# 06_POWER_2.net
KiCad netlist of a schematic drawn in Altium Designer
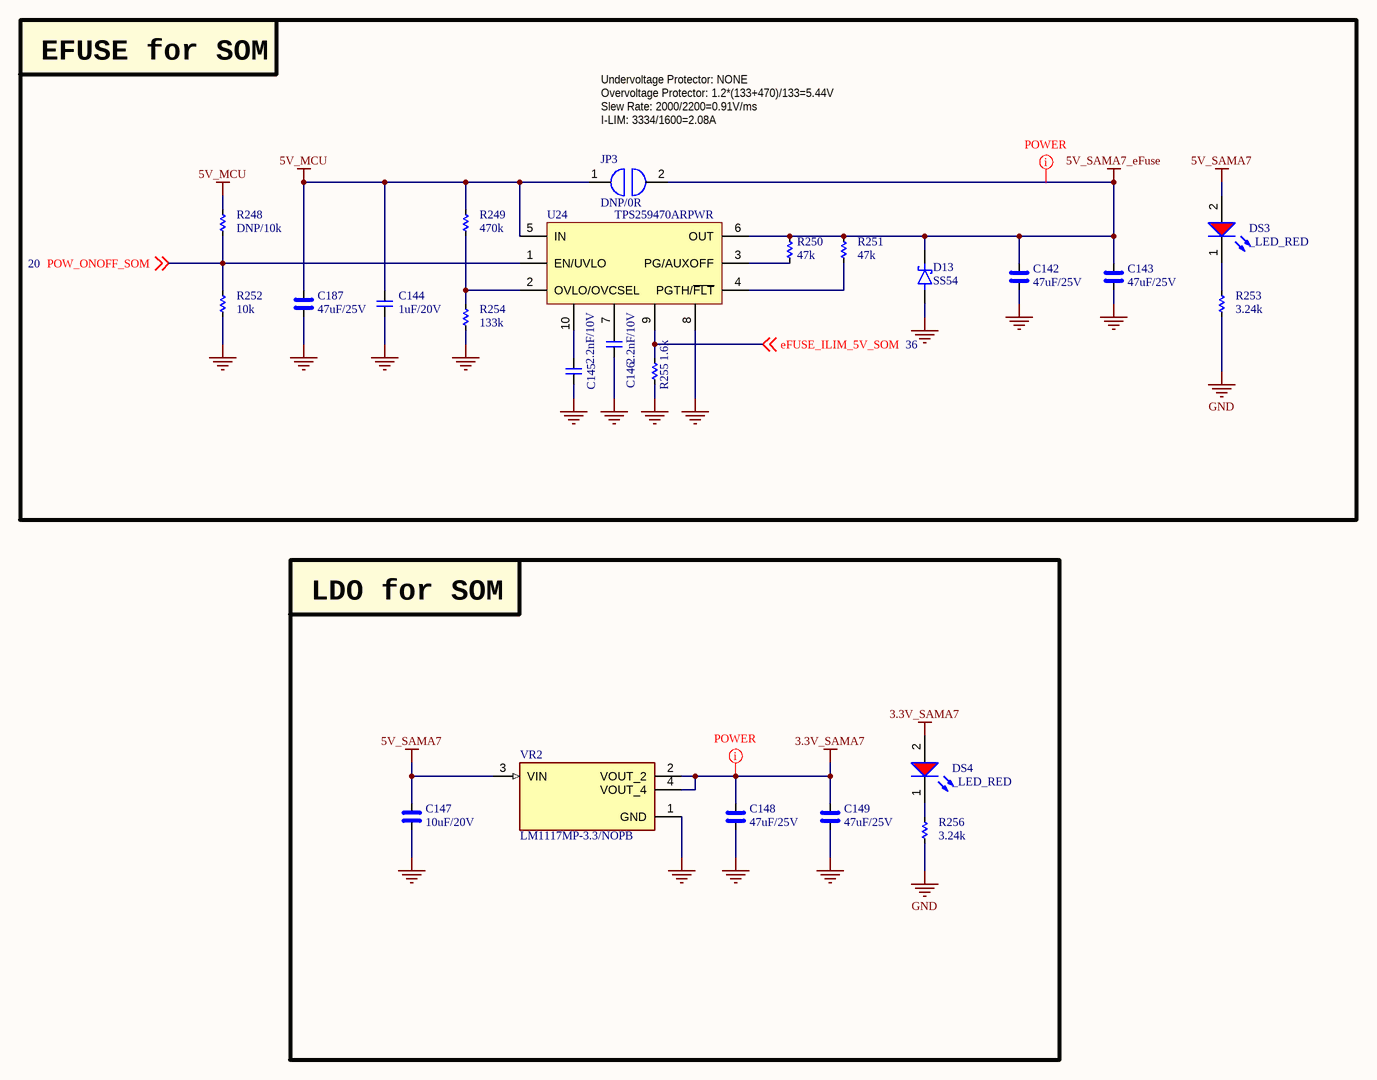
[diagram p0: 06_POWER_2.SchDoc]

(export (version "E")
  (design (tool "Eeschema 10.0.6"))
  (components
    (comp (ref "C142")
      (value "47uF/25V")
      (footprint "CAP_C_3225X80")
      (description "CAP High Value")
      (libsource (lib "LABLIB") (part "_CAP_C_High_2"))
    )
    (comp (ref "C143")
      (value "47uF/25V")
      (footprint "CAP_C_3225X80")
      (description "CAP High Value")
      (libsource (lib "LABLIB") (part "_CAP_C_High_2"))
    )
    (comp (ref "C144")
      (value "1uF/20V")
      (footprint "CAP_C_1005X60")
      (description "CAP")
      (libsource (lib "LABLIB") (part "_CAP_C_2"))
    )
    (comp (ref "C145")
      (value "2.2nF/10V")
      (footprint "CAP_C_1005X60")
      (description "CAP")
      (libsource (lib "LABLIB") (part "_CAP_C_2"))
    )
    (comp (ref "C146")
      (value "2.2nF/10V")
      (footprint "CAP_C_1005X60")
      (description "CAP")
      (libsource (lib "LABLIB") (part "_CAP_C_2"))
    )
    (comp (ref "C147")
      (value "10uF/20V")
      (footprint "CAP_C_2012X110")
      (description "CAP High Value")
      (libsource (lib "LABLIB") (part "_CAP_C_High_2"))
    )
    (comp (ref "C148")
      (value "47uF/25V")
      (footprint "CAP_C_3225X80")
      (description "CAP High Value")
      (libsource (lib "LABLIB") (part "_CAP_C_High_2"))
    )
    (comp (ref "C149")
      (value "47uF/25V")
      (footprint "CAP_C_3225X80")
      (description "CAP High Value")
      (libsource (lib "LABLIB") (part "_CAP_C_High_2"))
    )
    (comp (ref "C187")
      (value "47uF/25V")
      (footprint "CAP_C_3225X80")
      (description "CAP High Value")
      (libsource (lib "LABLIB") (part "_CAP_C_High_2"))
    )
    (comp (ref "D13")
      (value "SS54")
      (footprint "DO-214AC_SMA")
      (description "DIODE SCHOTTKY")
      (libsource (lib "LABLIB") (part "DIODE SCHOTTKY"))
    )
    (comp (ref "DS3") (value "_LED_RED") (footprint "LED_0603") (libsource (lib "LABLIB") (part "_LED_RED")))
    (comp (ref "DS4") (value "_LED_RED") (footprint "LED_0603") (libsource (lib "LABLIB") (part "_LED_RED")))
    (comp (ref "JP3") (value "DNP/0R") (footprint "JUMPER_1608") (libsource (lib "EXP_V1") (part "JUMPER")))
    (comp (ref "R248")
      (value "DNP/10k")
      (footprint "RES_C_1005X40")
      (description "RES")
      (libsource (lib "LABLIB") (part "_RES_B_2"))
    )
    (comp (ref "R249")
      (value "470k")
      (footprint "RES_C_1005X40")
      (description "RES")
      (libsource (lib "LABLIB") (part "_RES_B_2"))
    )
    (comp (ref "R250")
      (value "47k")
      (footprint "RES_C_1005X40")
      (description "RES")
      (libsource (lib "LABLIB") (part "_RES_B_2"))
    )
    (comp (ref "R251")
      (value "47k")
      (footprint "RES_C_1005X40")
      (description "RES")
      (libsource (lib "LABLIB") (part "_RES_B_2"))
    )
    (comp (ref "R252")
      (value "10k")
      (footprint "RES_C_1005X40")
      (description "RES")
      (libsource (lib "LABLIB") (part "_RES_B_2"))
    )
    (comp (ref "R253")
      (value "3.24k")
      (footprint "RES_C_1005X40")
      (description "RES")
      (libsource (lib "LABLIB") (part "_RES_B_2"))
    )
    (comp (ref "R254")
      (value "133k")
      (footprint "RES_C_1005X40")
      (description "RES")
      (libsource (lib "LABLIB") (part "_RES_B_2"))
    )
    (comp (ref "R255")
      (value "1.6k")
      (footprint "RES_C_1005X40")
      (description "RES")
      (libsource (lib "LABLIB") (part "_RES_B_2"))
    )
    (comp (ref "R256")
      (value "3.24k")
      (footprint "RES_C_1005X40")
      (description "RES")
      (libsource (lib "LABLIB") (part "_RES_B_2"))
    )
    (comp (ref "U24")
      (value "TPS259470ARPWR")
      (footprint "VQFN-HR-10")
      (libsource (lib "EXP_HW_V3") (part "TPS259470ARPWR"))
    )
    (comp (ref "VR2")
      (value "LM1117MP-3.3/NOPB")
      (footprint "VREG_LM1117MP-3.3/NOPB")
      (description "800-mA 15-V linear voltage regulator")
      (fields (field (name "MF") "Texas Instruments"))
      (libsource (lib "LABLIB") (part "LM1117MP-3.3/NOPB"))
    )
  )
  (nets
    (net (code "1") (name "3.3V_SAMA7") (class "Default")
      (node (ref "C148") (pin "2") (pinfunction "2_2") (pintype "passive"))
      (node (ref "C149") (pin "2") (pinfunction "2_2") (pintype "passive"))
      (node (ref "DS4") (pin "2") (pinfunction "A_2") (pintype "passive"))
      (node (ref "VR2") (pin "2") (pinfunction "VOUT_2_2") (pintype "power_in"))
      (node (ref "VR2") (pin "4") (pinfunction "VOUT_4_4") (pintype "power_in"))
    )
    (net (code "2") (name "5V_MCU") (class "Default")
      (node (ref "C144") (pin "2") (pinfunction "2_2") (pintype "passive"))
      (node (ref "C187") (pin "2") (pinfunction "2_2") (pintype "passive"))
      (node (ref "JP3") (pin "1") (pinfunction "1_1") (pintype "passive"))
      (node (ref "R248") (pin "1") (pinfunction "1_1") (pintype "passive"))
      (node (ref "R249") (pin "2") (pinfunction "2_2") (pintype "passive"))
      (node (ref "U24") (pin "5") (pinfunction "IN_5") (pintype "passive"))
    )
    (net (code "3") (name "5V_SAMA7") (class "Default")
      (node (ref "C147") (pin "1") (pinfunction "1_1") (pintype "passive"))
      (node (ref "DS3") (pin "2") (pinfunction "A_2") (pintype "passive"))
      (node (ref "VR2") (pin "3") (pinfunction "VIN_3") (pintype "input"))
    )
    (net (code "4") (name "5V_SAMA7_eFuse") (class "Default")
      (node (ref "C142") (pin "2") (pinfunction "2_2") (pintype "passive"))
      (node (ref "C143") (pin "2") (pinfunction "2_2") (pintype "passive"))
      (node (ref "D13") (pin "1") (pinfunction "K_1") (pintype "passive"))
      (node (ref "JP3") (pin "2") (pinfunction "2_2") (pintype "passive"))
      (node (ref "R250") (pin "2") (pinfunction "2_2") (pintype "passive"))
      (node (ref "R251") (pin "2") (pinfunction "2_2") (pintype "passive"))
      (node (ref "U24") (pin "6") (pinfunction "OUT_6") (pintype "passive"))
    )
    (net (code "5") (name "GND") (class "Default")
      (node (ref "C142") (pin "1") (pinfunction "1_1") (pintype "passive"))
      (node (ref "C143") (pin "1") (pinfunction "1_1") (pintype "passive"))
      (node (ref "C144") (pin "1") (pinfunction "1_1") (pintype "passive"))
      (node (ref "C145") (pin "1") (pinfunction "1_1") (pintype "passive"))
      (node (ref "C146") (pin "1") (pinfunction "1_1") (pintype "passive"))
      (node (ref "C147") (pin "2") (pinfunction "2_2") (pintype "passive"))
      (node (ref "C148") (pin "1") (pinfunction "1_1") (pintype "passive"))
      (node (ref "C149") (pin "1") (pinfunction "1_1") (pintype "passive"))
      (node (ref "C187") (pin "1") (pinfunction "1_1") (pintype "passive"))
      (node (ref "D13") (pin "2") (pinfunction "A_2") (pintype "passive"))
      (node (ref "R252") (pin "2") (pinfunction "2_2") (pintype "passive"))
      (node (ref "R253") (pin "1") (pinfunction "1_1") (pintype "passive"))
      (node (ref "R254") (pin "1") (pinfunction "1_1") (pintype "passive"))
      (node (ref "R255") (pin "1") (pinfunction "1_1") (pintype "passive"))
      (node (ref "R256") (pin "1") (pinfunction "1_1") (pintype "passive"))
      (node (ref "U24") (pin "8") (pinfunction "8_8") (pintype "passive"))
      (node (ref "VR2") (pin "1") (pinfunction "GND_1") (pintype "power_in"))
    )
    (net (code "6") (name "Net-(C145-Pad2)") (class "Default")
      (node (ref "C145") (pin "2") (pinfunction "2_2") (pintype "passive"))
      (node (ref "U24") (pin "10") (pinfunction "10_10") (pintype "passive"))
    )
    (net (code "7") (name "Net-(C146-Pad2)") (class "Default")
      (node (ref "C146") (pin "2") (pinfunction "2_2") (pintype "passive"))
      (node (ref "U24") (pin "7") (pinfunction "7_7") (pintype "passive"))
    )
    (net (code "8") (name "Net-(DS3-K)") (class "Default")
      (node (ref "DS3") (pin "1") (pinfunction "K_1") (pintype "passive"))
      (node (ref "R253") (pin "2") (pinfunction "2_2") (pintype "passive"))
    )
    (net (code "9") (name "Net-(DS4-K)") (class "Default")
      (node (ref "DS4") (pin "1") (pinfunction "K_1") (pintype "passive"))
      (node (ref "R256") (pin "2") (pinfunction "2_2") (pintype "passive"))
    )
    (net (code "10") (name "Net-(U24-OVLO{slash}OVCSEL)") (class "Default")
      (node (ref "R249") (pin "1") (pinfunction "1_1") (pintype "passive"))
      (node (ref "R254") (pin "2") (pinfunction "2_2") (pintype "passive"))
      (node (ref "U24") (pin "2") (pinfunction "OVLO/OVCSEL_2") (pintype "passive"))
    )
    (net (code "11") (name "Net-(U24-PGTH{slash}~{FLT})") (class "Default")
      (node (ref "R251") (pin "1") (pinfunction "1_1") (pintype "passive"))
      (node (ref "U24") (pin "4") (pinfunction "PGTH/~{FLT}_4") (pintype "passive"))
    )
    (net (code "12") (name "Net-(U24-PG{slash}AUXOFF)") (class "Default")
      (node (ref "R250") (pin "1") (pinfunction "1_1") (pintype "passive"))
      (node (ref "U24") (pin "3") (pinfunction "PG/AUXOFF_3") (pintype "passive"))
    )
    (net (code "13") (name "POW_ONOFF_SOM") (class "Default")
      (node (ref "R248") (pin "2") (pinfunction "2_2") (pintype "passive"))
      (node (ref "R252") (pin "1") (pinfunction "1_1") (pintype "passive"))
      (node (ref "U24") (pin "1") (pinfunction "EN/UVLO_1") (pintype "passive"))
    )
    (net (code "14") (name "eFUSE_ILIM_5V_SOM") (class "Default")
      (node (ref "R255") (pin "2") (pinfunction "2_2") (pintype "passive"))
      (node (ref "U24") (pin "9") (pinfunction "9_9") (pintype "passive"))
    )
  )
)
